# MotorDriverSchm.net
KiCad netlist of a schematic drawn in Altium Designer
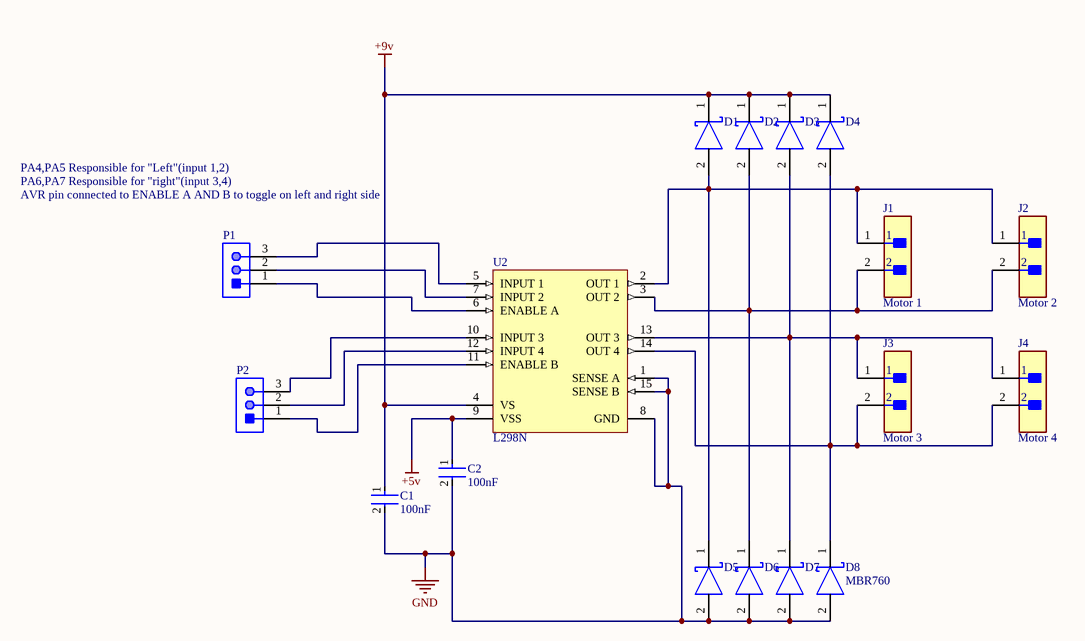
[diagram p0: MotorDriverSchm.SchDoc]

(export (version "E")
  (design (tool "Eeschema 10.0.6"))
  (components
    (comp (ref "C1")
      (value "100nF")
      (footprint "FP-K15H5-MFG")
      (description "CAP CER 0.1UF 50V X7R RADIAL")
      (fields (field (name "TOLERANCE") "10%") (field (name "VOLTAGE") "50V"))
      (libsource (lib "Altium Content Vault") (part "02cd4be3c70576c341d710602a673aa"))
    )
    (comp (ref "C2")
      (value "100nF")
      (footprint "FP-K15H5-MFG")
      (description "CAP CER 0.1UF 50V X7R RADIAL")
      (fields (field (name "TOLERANCE") "10%") (field (name "VOLTAGE") "50V"))
      (libsource (lib "Altium Content Vault") (part "02cd4be3c70576c341d710602a673aa"))
    )
    (comp (ref "D1")
      (value "~")
      (footprint "FP-340BA-MFG")
      (description "MBR760 Diode Schottky 60V 7.5A 2-Pin(2+Tab) TO-220AC Rail")
      (libsource (lib "Altium Content Vault") (part "a071e5edd1fb65b81e22f681b9e141c"))
    )
    (comp (ref "D2")
      (value "~")
      (footprint "FP-340BA-MFG")
      (description "MBR760 Diode Schottky 60V 7.5A 2-Pin(2+Tab) TO-220AC Rail")
      (libsource (lib "Altium Content Vault") (part "a071e5edd1fb65b81e22f681b9e141c"))
    )
    (comp (ref "D3")
      (value "~")
      (footprint "FP-340BA-MFG")
      (description "MBR760 Diode Schottky 60V 7.5A 2-Pin(2+Tab) TO-220AC Rail")
      (libsource (lib "Altium Content Vault") (part "a071e5edd1fb65b81e22f681b9e141c"))
    )
    (comp (ref "D4")
      (value "~")
      (footprint "FP-340BA-MFG")
      (description "MBR760 Diode Schottky 60V 7.5A 2-Pin(2+Tab) TO-220AC Rail")
      (libsource (lib "Altium Content Vault") (part "a071e5edd1fb65b81e22f681b9e141c"))
    )
    (comp (ref "D5")
      (value "~")
      (footprint "FP-340BA-MFG")
      (description "MBR760 Diode Schottky 60V 7.5A 2-Pin(2+Tab) TO-220AC Rail")
      (libsource (lib "Altium Content Vault") (part "a071e5edd1fb65b81e22f681b9e141c"))
    )
    (comp (ref "D6")
      (value "~")
      (footprint "FP-340BA-MFG")
      (description "MBR760 Diode Schottky 60V 7.5A 2-Pin(2+Tab) TO-220AC Rail")
      (libsource (lib "Altium Content Vault") (part "a071e5edd1fb65b81e22f681b9e141c"))
    )
    (comp (ref "D7")
      (value "~")
      (footprint "FP-340BA-MFG")
      (description "MBR760 Diode Schottky 60V 7.5A 2-Pin(2+Tab) TO-220AC Rail")
      (libsource (lib "Altium Content Vault") (part "a071e5edd1fb65b81e22f681b9e141c"))
    )
    (comp (ref "D8")
      (value "MBR760")
      (footprint "FP-340BA-MFG")
      (description "MBR760 Diode Schottky 60V 7.5A 2-Pin(2+Tab) TO-220AC Rail")
      (libsource (lib "Altium Content Vault") (part "a071e5edd1fb65b81e22f681b9e141c"))
    )
    (comp (ref "J1")
      (value "Motor 1")
      (footprint "FP-M20-9990246-MFG")
      (description "CONN HEADER VERT 2POS 2.54MM")
      (fields
        (field (name "OCTOPART") "https://octopart.com/m20-9990246-harwin-2590635")
        (field (name "MANUFACTURER") "Harwin")
      )
      (libsource (lib "Altium Content Vault") (part "3bc925449376181038e59eaffc5286c"))
    )
    (comp (ref "J2")
      (value "Motor 2")
      (footprint "FP-M20-9990246-MFG")
      (description "CONN HEADER VERT 2POS 2.54MM")
      (fields
        (field (name "OCTOPART") "https://octopart.com/m20-9990246-harwin-2590635")
        (field (name "MANUFACTURER") "Harwin")
      )
      (libsource (lib "Altium Content Vault") (part "3bc925449376181038e59eaffc5286c"))
    )
    (comp (ref "J3")
      (value "Motor 3")
      (footprint "FP-M20-9990246-MFG")
      (description "CONN HEADER VERT 2POS 2.54MM")
      (fields
        (field (name "OCTOPART") "https://octopart.com/m20-9990246-harwin-2590635")
        (field (name "MANUFACTURER") "Harwin")
      )
      (libsource (lib "Altium Content Vault") (part "3bc925449376181038e59eaffc5286c"))
    )
    (comp (ref "J4")
      (value "Motor 4")
      (footprint "FP-M20-9990246-MFG")
      (description "CONN HEADER VERT 2POS 2.54MM")
      (fields
        (field (name "OCTOPART") "https://octopart.com/m20-9990246-harwin-2590635")
        (field (name "MANUFACTURER") "Harwin")
      )
      (libsource (lib "Altium Content Vault") (part "3bc925449376181038e59eaffc5286c"))
    )
    (comp (ref "P1")
      (value "~")
      (footprint "MOLX-22-28-4033_V")
      (description "Male Header, Pitch 2.54 mm, 1 x 3 Position, Height 8.38 mm, Tail Length 3.18 mm, RoHS, Bulk")
      (fields (field (name "MANUFACTURER") "Molex"))
      (libsource (lib "Altium Content Vault") (part "CN-1P-M-R3"))
    )
    (comp (ref "P2")
      (value "~")
      (footprint "MOLX-22-28-4033_V")
      (description "Male Header, Pitch 2.54 mm, 1 x 3 Position, Height 8.38 mm, Tail Length 3.18 mm, RoHS, Bulk")
      (fields (field (name "MANUFACTURER") "Molex"))
      (libsource (lib "Altium Content Vault") (part "CN-1P-M-R3"))
    )
    (comp (ref "U2")
      (value "L298N")
      (footprint "STM-FM-15")
      (description "Dual Full-Bridge Driver, 4.8 to 46 V, -40 to 150 degC, 15-Pin FM (MW 15L), RoHS, Tube")
      (fields (field (name "MANUFACTURER") "STMicroelectronics") (field (name "PARTNUMBER") "L298"))
      (libsource (lib "Altium Content Vault") (part "STM-L298-15"))
    )
  )
  (nets
    (net (code "1") (name "+5v") (class "Default")
      (node (ref "C2") (pin "1") (pinfunction "1_1") (pintype "passive"))
      (node (ref "U2") (pin "9") (pinfunction "VSS_9") (pintype "power_in"))
    )
    (net (code "2") (name "+9v") (class "Default")
      (node (ref "C1") (pin "1") (pinfunction "1_1") (pintype "passive"))
      (node (ref "D1") (pin "1") (pinfunction "C_1") (pintype "passive"))
      (node (ref "D2") (pin "1") (pinfunction "C_1") (pintype "passive"))
      (node (ref "D3") (pin "1") (pinfunction "C_1") (pintype "passive"))
      (node (ref "D4") (pin "1") (pinfunction "C_1") (pintype "passive"))
      (node (ref "U2") (pin "4") (pinfunction "VS_4") (pintype "power_in"))
    )
    (net (code "3") (name "GND") (class "Default")
      (node (ref "C1") (pin "2") (pinfunction "2_2") (pintype "passive"))
      (node (ref "C2") (pin "2") (pinfunction "2_2") (pintype "passive"))
      (node (ref "D5") (pin "2") (pinfunction "A_2") (pintype "passive"))
      (node (ref "D6") (pin "2") (pinfunction "A_2") (pintype "passive"))
      (node (ref "D7") (pin "2") (pinfunction "A_2") (pintype "passive"))
      (node (ref "D8") (pin "2") (pinfunction "A_2") (pintype "passive"))
      (node (ref "U2") (pin "1") (pinfunction "SENSE_A_1") (pintype "input"))
      (node (ref "U2") (pin "15") (pinfunction "SENSE_B_15") (pintype "input"))
      (node (ref "U2") (pin "8") (pinfunction "GND_8") (pintype "power_in"))
    )
    (net (code "4") (name "Net-(D1-A)") (class "Default")
      (node (ref "D1") (pin "2") (pinfunction "A_2") (pintype "passive"))
      (node (ref "D5") (pin "1") (pinfunction "C_1") (pintype "passive"))
      (node (ref "J1") (pin "1") (pinfunction "1_1") (pintype "passive"))
      (node (ref "J2") (pin "1") (pinfunction "1_1") (pintype "passive"))
      (node (ref "U2") (pin "2") (pinfunction "OUT_1_2") (pintype "output"))
    )
    (net (code "5") (name "Net-(D2-A)") (class "Default")
      (node (ref "D2") (pin "2") (pinfunction "A_2") (pintype "passive"))
      (node (ref "D6") (pin "1") (pinfunction "C_1") (pintype "passive"))
      (node (ref "J1") (pin "2") (pinfunction "2_2") (pintype "passive"))
      (node (ref "J2") (pin "2") (pinfunction "2_2") (pintype "passive"))
      (node (ref "U2") (pin "3") (pinfunction "OUT_2_3") (pintype "output"))
    )
    (net (code "6") (name "Net-(D3-A)") (class "Default")
      (node (ref "D3") (pin "2") (pinfunction "A_2") (pintype "passive"))
      (node (ref "D7") (pin "1") (pinfunction "C_1") (pintype "passive"))
      (node (ref "J3") (pin "1") (pinfunction "1_1") (pintype "passive"))
      (node (ref "J4") (pin "1") (pinfunction "1_1") (pintype "passive"))
      (node (ref "U2") (pin "13") (pinfunction "OUT_3_13") (pintype "output"))
    )
    (net (code "7") (name "Net-(D4-A)") (class "Default")
      (node (ref "D4") (pin "2") (pinfunction "A_2") (pintype "passive"))
      (node (ref "D8") (pin "1") (pinfunction "C_1") (pintype "passive"))
      (node (ref "J3") (pin "2") (pinfunction "2_2") (pintype "passive"))
      (node (ref "J4") (pin "2") (pinfunction "2_2") (pintype "passive"))
      (node (ref "U2") (pin "14") (pinfunction "OUT_4_14") (pintype "output"))
    )
    (net (code "8") (name "Net-(U2-ENABLE_A)") (class "Default")
      (node (ref "P1") (pin "1") (pinfunction "1_1") (pintype "passive"))
      (node (ref "U2") (pin "6") (pinfunction "ENABLE_A_6") (pintype "input"))
    )
    (net (code "9") (name "Net-(U2-ENABLE_B)") (class "Default")
      (node (ref "P2") (pin "1") (pinfunction "1_1") (pintype "passive"))
      (node (ref "U2") (pin "11") (pinfunction "ENABLE_B_11") (pintype "input"))
    )
    (net (code "10") (name "Net-(U2-INPUT_1)") (class "Default")
      (node (ref "P1") (pin "3") (pinfunction "3_3") (pintype "passive"))
      (node (ref "U2") (pin "5") (pinfunction "INPUT_1_5") (pintype "input"))
    )
    (net (code "11") (name "Net-(U2-INPUT_2)") (class "Default")
      (node (ref "P1") (pin "2") (pinfunction "2_2") (pintype "passive"))
      (node (ref "U2") (pin "7") (pinfunction "INPUT_2_7") (pintype "input"))
    )
    (net (code "12") (name "Net-(U2-INPUT_3)") (class "Default")
      (node (ref "P2") (pin "3") (pinfunction "3_3") (pintype "passive"))
      (node (ref "U2") (pin "10") (pinfunction "INPUT_3_10") (pintype "input"))
    )
    (net (code "13") (name "Net-(U2-INPUT_4)") (class "Default")
      (node (ref "P2") (pin "2") (pinfunction "2_2") (pintype "passive"))
      (node (ref "U2") (pin "12") (pinfunction "INPUT_4_12") (pintype "input"))
    )
  )
)
